# HW1_8.net
KiCad netlist of a schematic drawn in EasyEDA
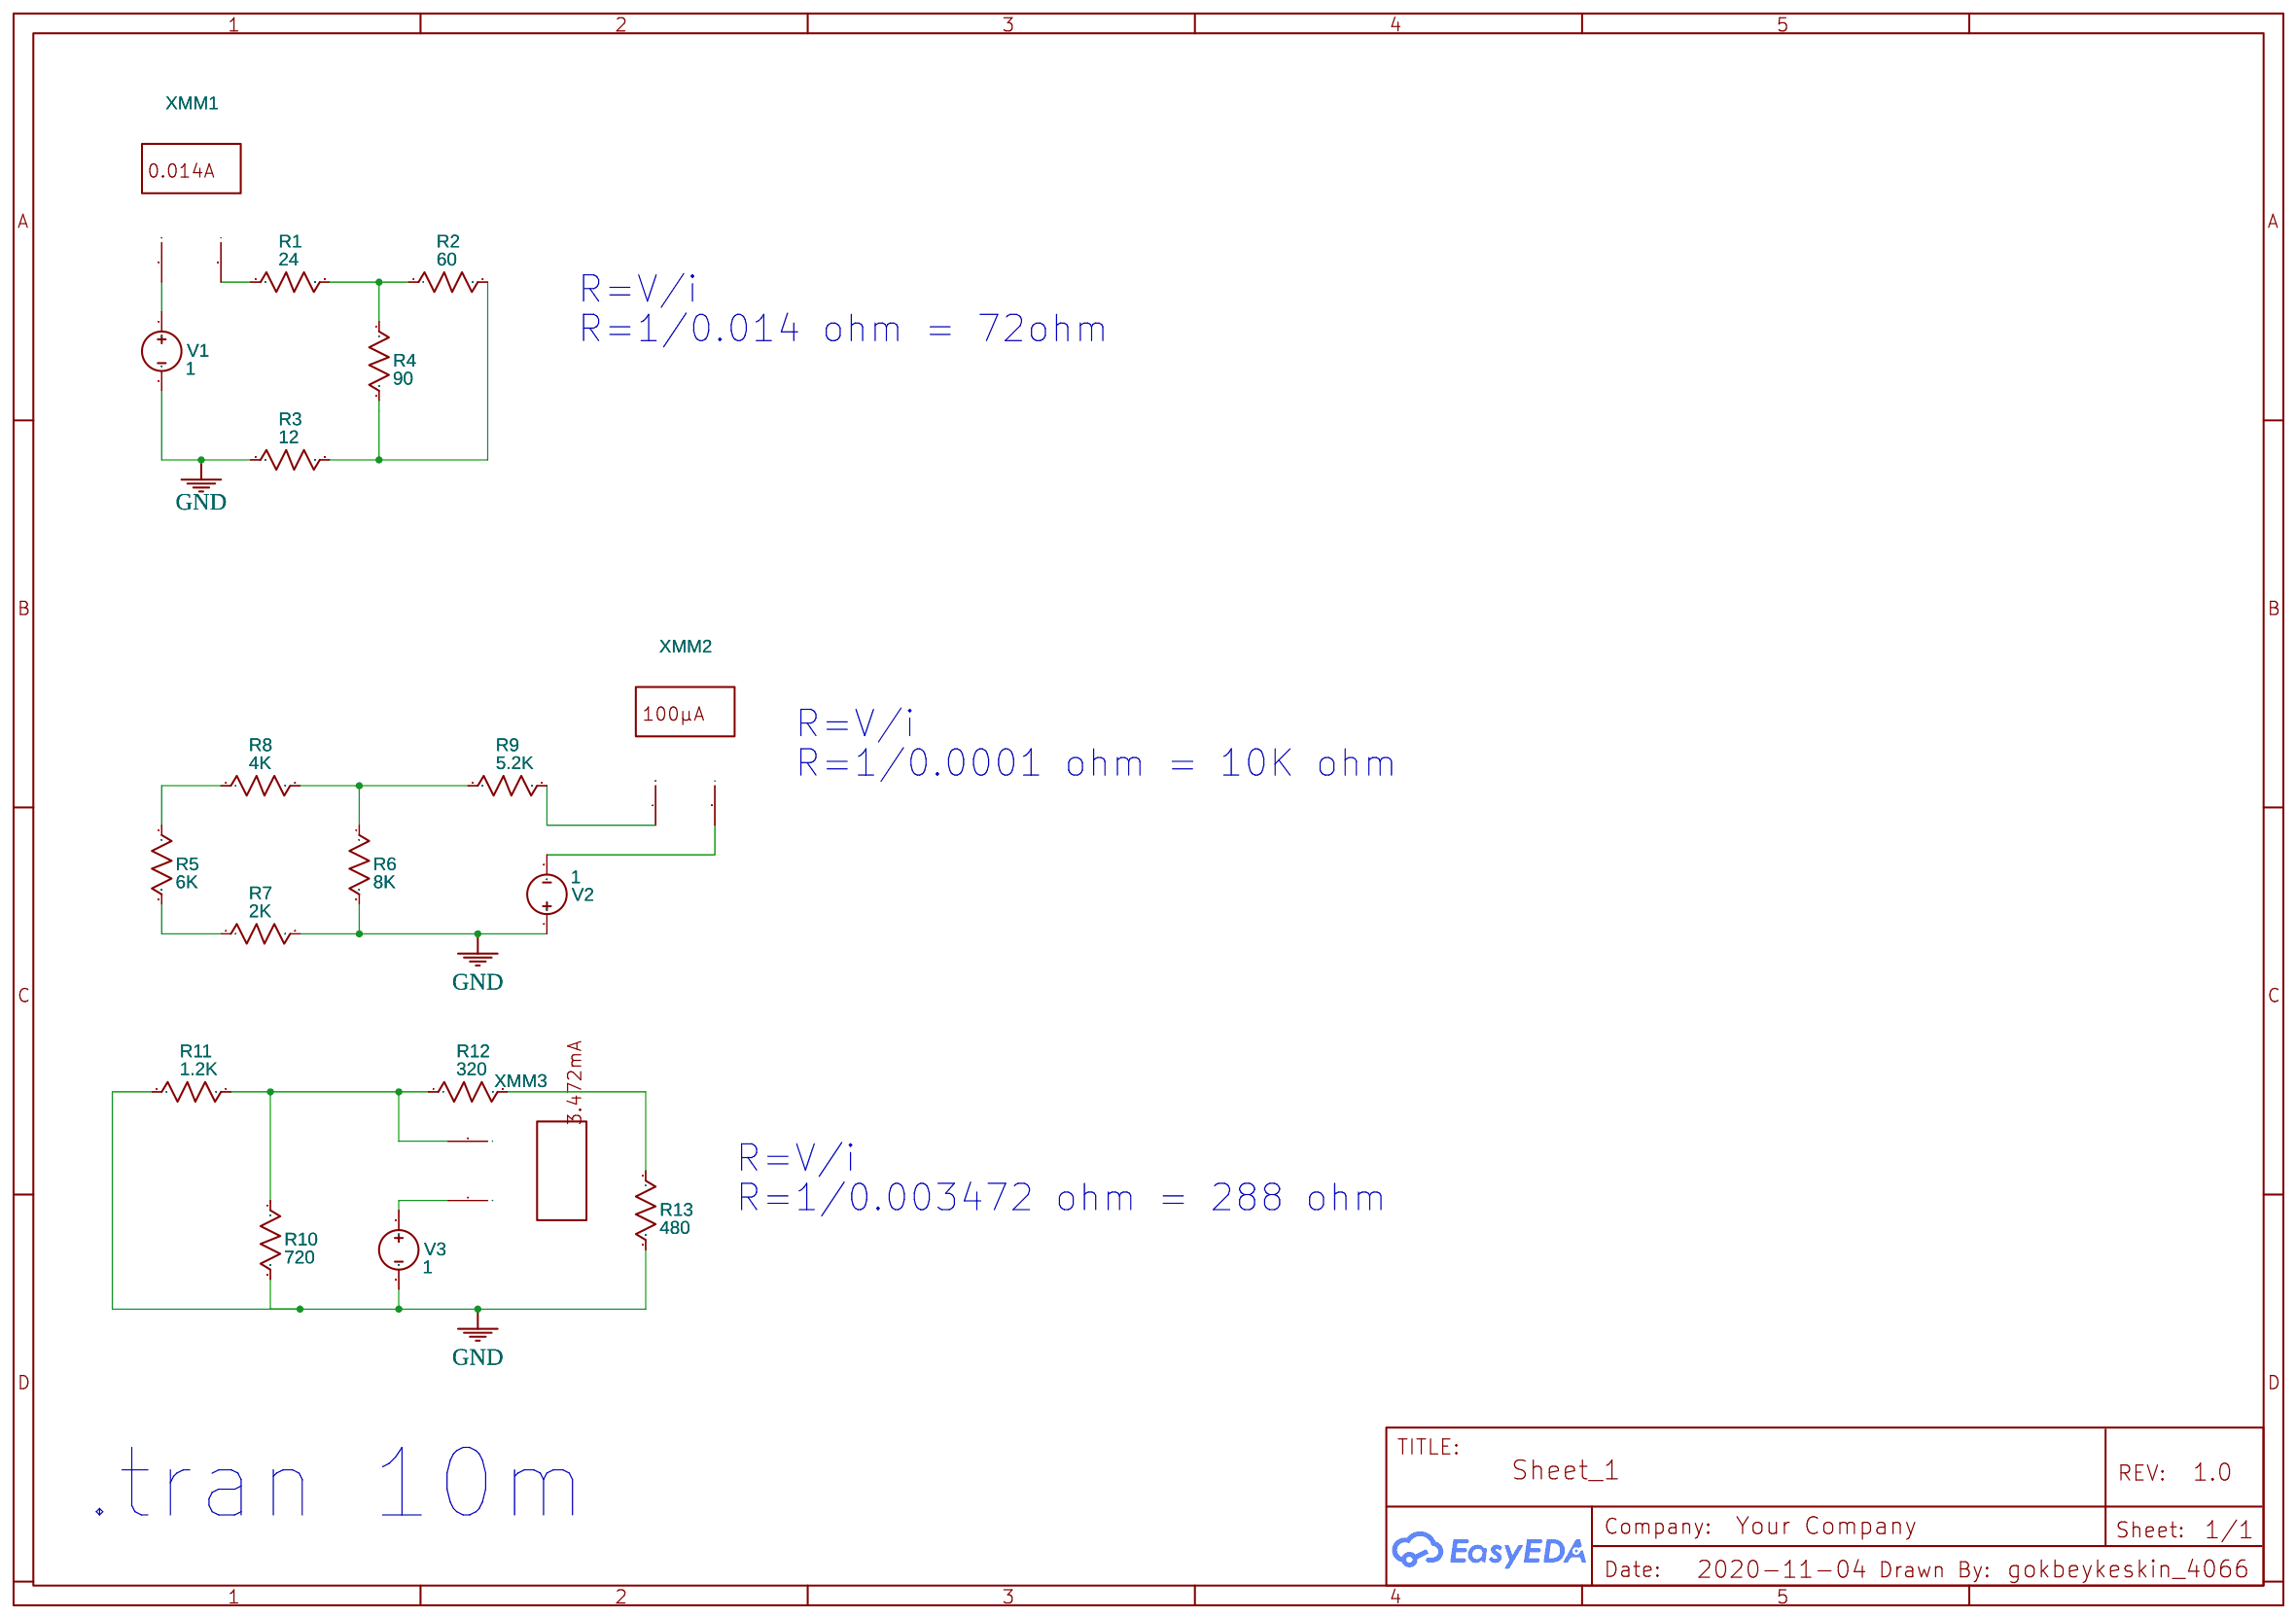
[diagram p0: schematic sheet]

(export (version "E")
  (design (tool "Eeschema 10.0.6"))
  (components
    (comp (ref "R1") (value "24") (libsource (lib "") (part "Resistor_US_1")))
    (comp (ref "R2") (value "60") (libsource (lib "") (part "Resistor_US_1")))
    (comp (ref "R3") (value "12") (libsource (lib "") (part "Resistor_US_1")))
    (comp (ref "R4") (value "90") (libsource (lib "") (part "Resistor_US")))
    (comp (ref "R5") (value "6K") (libsource (lib "") (part "Resistor_US")))
    (comp (ref "R6") (value "8K") (libsource (lib "") (part "Resistor_US")))
    (comp (ref "R7") (value "2K") (libsource (lib "") (part "Resistor_US_1")))
    (comp (ref "R8") (value "4K") (libsource (lib "") (part "Resistor_US_1")))
    (comp (ref "R9") (value "5.2K") (libsource (lib "") (part "Resistor_US_1")))
    (comp (ref "R10") (value "720") (libsource (lib "") (part "Resistor_US")))
    (comp (ref "R11") (value "1.2K") (libsource (lib "") (part "Resistor_US_1")))
    (comp (ref "R12") (value "320") (libsource (lib "") (part "Resistor_US_1")))
    (comp (ref "R13") (value "480") (libsource (lib "") (part "Resistor_US")))
    (comp (ref "V1") (value "1") (libsource (lib "") (part "VDC")))
    (comp (ref "V2") (value "1") (libsource (lib "") (part "VDC_1")))
    (comp (ref "V3") (value "1") (libsource (lib "") (part "VDC")))
    (comp (ref "XMM1") (value "Multimeter") (libsource (lib "") (part "MULTIMETER")))
    (comp (ref "XMM2") (value "Multimeter") (libsource (lib "") (part "MULTIMETER_1")))
    (comp (ref "XMM3") (value "Multimeter") (libsource (lib "") (part "MULTIMETER_2")))
  )
  (nets
    (net (code "1") (name "GND") (class "Default")
      (node (ref "R10") (pin "2") (pinfunction "2_2") (pintype "unspecified"))
      (node (ref "R11") (pin "1") (pinfunction "1_1") (pintype "unspecified"))
      (node (ref "R13") (pin "2") (pinfunction "2_2") (pintype "unspecified"))
      (node (ref "R3") (pin "1") (pinfunction "1_1") (pintype "unspecified"))
      (node (ref "R6") (pin "2") (pinfunction "2_2") (pintype "unspecified"))
      (node (ref "R7") (pin "2") (pinfunction "2_2") (pintype "unspecified"))
      (node (ref "V1") (pin "2") (pinfunction "2_2") (pintype "unspecified"))
      (node (ref "V2") (pin "1") (pinfunction "1_1") (pintype "unspecified"))
      (node (ref "V3") (pin "2") (pinfunction "2_2") (pintype "unspecified"))
    )
    (net (code "2") (name "Net-(R1-Pad2)") (class "Default")
      (node (ref "R1") (pin "2") (pinfunction "2_2") (pintype "unspecified"))
      (node (ref "R2") (pin "1") (pinfunction "1_1") (pintype "unspecified"))
      (node (ref "R4") (pin "1") (pinfunction "1_1") (pintype "unspecified"))
    )
    (net (code "3") (name "Net-(R2-Pad2)") (class "Default")
      (node (ref "R2") (pin "2") (pinfunction "2_2") (pintype "unspecified"))
      (node (ref "R3") (pin "2") (pinfunction "2_2") (pintype "unspecified"))
      (node (ref "R4") (pin "2") (pinfunction "2_2") (pintype "unspecified"))
    )
    (net (code "4") (name "Net-(R5-Pad1)") (class "Default")
      (node (ref "R5") (pin "1") (pinfunction "1_1") (pintype "unspecified"))
      (node (ref "R8") (pin "1") (pinfunction "1_1") (pintype "unspecified"))
    )
    (net (code "5") (name "Net-(R5-Pad2)") (class "Default")
      (node (ref "R5") (pin "2") (pinfunction "2_2") (pintype "unspecified"))
      (node (ref "R7") (pin "1") (pinfunction "1_1") (pintype "unspecified"))
    )
    (net (code "6") (name "Net-(R6-Pad1)") (class "Default")
      (node (ref "R6") (pin "1") (pinfunction "1_1") (pintype "unspecified"))
      (node (ref "R8") (pin "2") (pinfunction "2_2") (pintype "unspecified"))
      (node (ref "R9") (pin "1") (pinfunction "1_1") (pintype "unspecified"))
    )
    (net (code "7") (name "Net-(R12-Pad2)") (class "Default")
      (node (ref "R12") (pin "2") (pinfunction "2_2") (pintype "unspecified"))
      (node (ref "R13") (pin "1") (pinfunction "1_1") (pintype "unspecified"))
    )
    (net (code "8") (name "Net-(XMM1-+)") (class "Default")
      (node (ref "V1") (pin "1") (pinfunction "1_1") (pintype "unspecified"))
      (node (ref "XMM1") (pin "1") (pinfunction "+_1") (pintype "unspecified"))
    )
    (net (code "9") (name "Net-(XMM1-I)") (class "Default")
      (node (ref "R1") (pin "1") (pinfunction "1_1") (pintype "unspecified"))
      (node (ref "XMM1") (pin "2") (pinfunction "I_2") (pintype "unspecified"))
    )
    (net (code "10") (name "Net-(XMM2-+)") (class "Default")
      (node (ref "R9") (pin "2") (pinfunction "2_2") (pintype "unspecified"))
      (node (ref "XMM2") (pin "1") (pinfunction "+_1") (pintype "unspecified"))
    )
    (net (code "11") (name "Net-(XMM2-I)") (class "Default")
      (node (ref "V2") (pin "2") (pinfunction "2_2") (pintype "unspecified"))
      (node (ref "XMM2") (pin "2") (pinfunction "I_2") (pintype "unspecified"))
    )
    (net (code "12") (name "Net-(XMM3-+)") (class "Default")
      (node (ref "V3") (pin "1") (pinfunction "1_1") (pintype "unspecified"))
      (node (ref "XMM3") (pin "1") (pinfunction "+_1") (pintype "unspecified"))
    )
    (net (code "13") (name "Net-(XMM3-I)") (class "Default")
      (node (ref "R10") (pin "1") (pinfunction "1_1") (pintype "unspecified"))
      (node (ref "R11") (pin "2") (pinfunction "2_2") (pintype "unspecified"))
      (node (ref "R12") (pin "1") (pinfunction "1_1") (pintype "unspecified"))
      (node (ref "XMM3") (pin "2") (pinfunction "I_2") (pintype "unspecified"))
    )
  )
)
